# ESP32.net
KiCad netlist of a schematic drawn in EAGLE
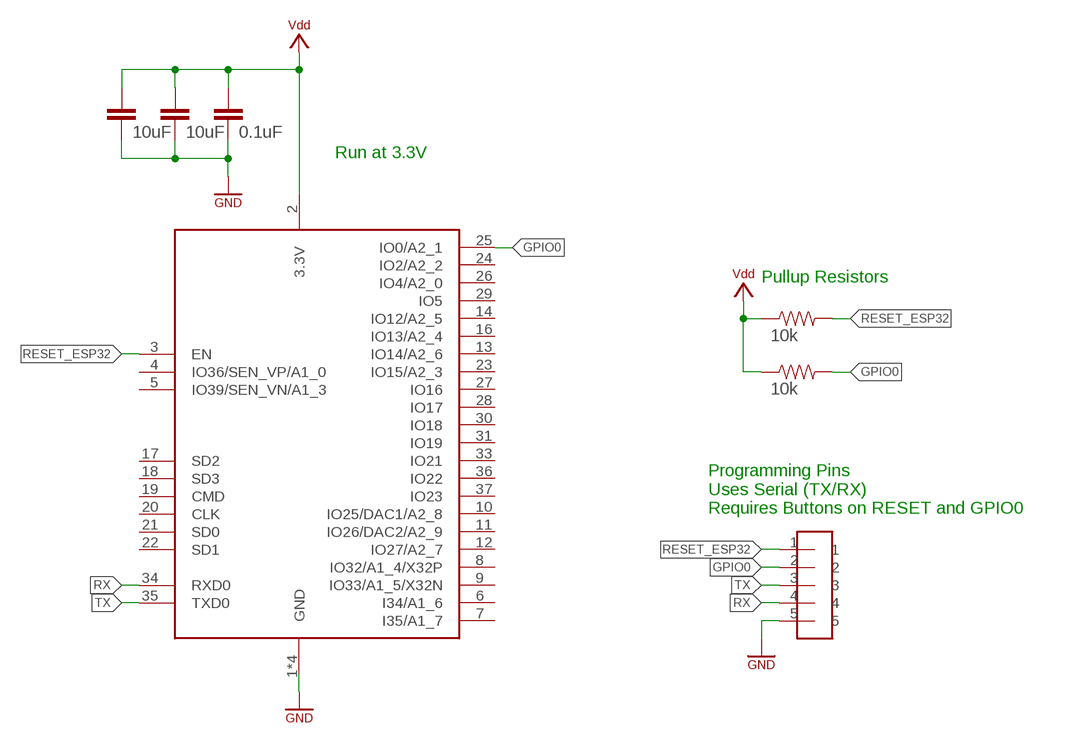
[diagram p0: schematic, sheet 1]

(export (version "E")
  (design (tool "Eeschema 10.0.6"))
  (components
    (comp (ref "C1")
      (value "0.1uF")
      (footprint "eagle-import:0805")
      (libsource (lib "eagle-import") (part "COMPONENT_CAP-0805"))
    )
    (comp (ref "C2")
      (value "10uF")
      (footprint "eagle-import:0805")
      (libsource (lib "eagle-import") (part "COMPONENT_CAP-0805"))
    )
    (comp (ref "C3")
      (value "10uF")
      (footprint "eagle-import:0805")
      (libsource (lib "eagle-import") (part "COMPONENT_CAP-0805"))
    )
    (comp (ref "R1")
      (value "10k")
      (footprint "eagle-import:0805")
      (libsource (lib "eagle-import") (part "COMPONENT_RESISTOR-0805"))
    )
    (comp (ref "R2")
      (value "10k")
      (footprint "eagle-import:0805")
      (libsource (lib "eagle-import") (part "COMPONENT_RESISTOR-0805"))
    )
    (comp (ref "U$1")
      (value "HEADER-5-TESTPOINT")
      (footprint "eagle-import:TESTPOINT-5")
      (libsource (lib "eagle-import") (part "HEADER-5-TESTPOINT"))
    )
    (comp (ref "X1")
      (value "MICRO_ESP32")
      (footprint "eagle-import:WROOM32")
      (libsource (lib "eagle-import") (part "MICRO_ESP32"))
    )
  )
  (nets
    (net (code "1") (name "GPIO0") (class "Default")
      (node (ref "R2") (pin "2") (pinfunction "2_2") (pintype "passive"))
      (node (ref "U$1") (pin "2") (pinfunction "2_2") (pintype "bidirectional"))
      (node (ref "X1") (pin "25") (pinfunction "IO0/A2_1_25") (pintype "bidirectional"))
    )
    (net (code "2") (name "RESET_ESP32") (class "Default")
      (node (ref "R1") (pin "2") (pinfunction "2_2") (pintype "passive"))
      (node (ref "U$1") (pin "1") (pinfunction "1_1") (pintype "bidirectional"))
      (node (ref "X1") (pin "3") (pinfunction "EN_3") (pintype "input"))
    )
    (net (code "3") (name "RX") (class "Default")
      (node (ref "U$1") (pin "4") (pinfunction "4_4") (pintype "bidirectional"))
      (node (ref "X1") (pin "34") (pinfunction "RXD0_34") (pintype "input"))
    )
    (net (code "4") (name "SYMBOL_GND") (class "Default")
      (node (ref "C1") (pin "2") (pinfunction "2_2") (pintype "passive"))
      (node (ref "C2") (pin "2") (pinfunction "2_2") (pintype "passive"))
      (node (ref "C3") (pin "2") (pinfunction "2_2") (pintype "passive"))
      (node (ref "U$1") (pin "5") (pinfunction "5_5") (pintype "bidirectional"))
      (node (ref "X1") (pin "1") (pinfunction "GND_1") (pintype "passive"))
      (node (ref "X1") (pin "15") (pinfunction "GND_15") (pintype "passive"))
      (node (ref "X1") (pin "38") (pinfunction "GND_38") (pintype "passive"))
      (node (ref "X1") (pin "P$1") (pinfunction "GND_P$1") (pintype "passive"))
    )
    (net (code "5") (name "SYMBOL_VDD") (class "Default")
      (node (ref "C1") (pin "1") (pinfunction "1_1") (pintype "passive"))
      (node (ref "C2") (pin "1") (pinfunction "1_1") (pintype "passive"))
      (node (ref "C3") (pin "1") (pinfunction "1_1") (pintype "passive"))
      (node (ref "R1") (pin "1") (pinfunction "1_1") (pintype "passive"))
      (node (ref "R2") (pin "1") (pinfunction "1_1") (pintype "passive"))
      (node (ref "X1") (pin "2") (pinfunction "3.3V_2") (pintype "passive"))
    )
    (net (code "6") (name "TX") (class "Default")
      (node (ref "U$1") (pin "3") (pinfunction "3_3") (pintype "bidirectional"))
      (node (ref "X1") (pin "35") (pinfunction "TXD0_35") (pintype "output"))
    )
    (net (code "7") (name "unconnected-(X1-CLK-Pad20)") (class "Default")
      (node (ref "X1") (pin "20") (pinfunction "CLK_20") (pintype "bidirectional"))
    )
    (net (code "8") (name "unconnected-(X1-CMD-Pad19)") (class "Default")
      (node (ref "X1") (pin "19") (pinfunction "CMD_19") (pintype "bidirectional"))
    )
    (net (code "9") (name "unconnected-(X1-I34{slash}A1_6-Pad6)") (class "Default")
      (node (ref "X1") (pin "6") (pinfunction "I34/A1_6_6") (pintype "bidirectional"))
    )
    (net (code "10") (name "unconnected-(X1-I35{slash}A1_7-Pad7)") (class "Default")
      (node (ref "X1") (pin "7") (pinfunction "I35/A1_7_7") (pintype "bidirectional"))
    )
    (net (code "11") (name "unconnected-(X1-IO2{slash}A2_2-Pad24)") (class "Default")
      (node (ref "X1") (pin "24") (pinfunction "IO2/A2_2_24") (pintype "bidirectional"))
    )
    (net (code "12") (name "unconnected-(X1-IO4{slash}A2_0-Pad26)") (class "Default")
      (node (ref "X1") (pin "26") (pinfunction "IO4/A2_0_26") (pintype "bidirectional"))
    )
    (net (code "13") (name "unconnected-(X1-IO5-Pad29)") (class "Default")
      (node (ref "X1") (pin "29") (pinfunction "IO5_29") (pintype "bidirectional"))
    )
    (net (code "14") (name "unconnected-(X1-IO12{slash}A2_5-Pad14)") (class "Default")
      (node (ref "X1") (pin "14") (pinfunction "IO12/A2_5_14") (pintype "bidirectional"))
    )
    (net (code "15") (name "unconnected-(X1-IO13{slash}A2_4-Pad16)") (class "Default")
      (node (ref "X1") (pin "16") (pinfunction "IO13/A2_4_16") (pintype "bidirectional"))
    )
    (net (code "16") (name "unconnected-(X1-IO14{slash}A2_6-Pad13)") (class "Default")
      (node (ref "X1") (pin "13") (pinfunction "IO14/A2_6_13") (pintype "bidirectional"))
    )
    (net (code "17") (name "unconnected-(X1-IO15{slash}A2_3-Pad23)") (class "Default")
      (node (ref "X1") (pin "23") (pinfunction "IO15/A2_3_23") (pintype "bidirectional"))
    )
    (net (code "18") (name "unconnected-(X1-IO16-Pad27)") (class "Default")
      (node (ref "X1") (pin "27") (pinfunction "IO16_27") (pintype "bidirectional"))
    )
    (net (code "19") (name "unconnected-(X1-IO17-Pad28)") (class "Default")
      (node (ref "X1") (pin "28") (pinfunction "IO17_28") (pintype "bidirectional"))
    )
    (net (code "20") (name "unconnected-(X1-IO18-Pad30)") (class "Default")
      (node (ref "X1") (pin "30") (pinfunction "IO18_30") (pintype "bidirectional"))
    )
    (net (code "21") (name "unconnected-(X1-IO19-Pad31)") (class "Default")
      (node (ref "X1") (pin "31") (pinfunction "IO19_31") (pintype "bidirectional"))
    )
    (net (code "22") (name "unconnected-(X1-IO21-Pad33)") (class "Default")
      (node (ref "X1") (pin "33") (pinfunction "IO21_33") (pintype "bidirectional"))
    )
    (net (code "23") (name "unconnected-(X1-IO22-Pad36)") (class "Default")
      (node (ref "X1") (pin "36") (pinfunction "IO22_36") (pintype "bidirectional"))
    )
    (net (code "24") (name "unconnected-(X1-IO23-Pad37)") (class "Default")
      (node (ref "X1") (pin "37") (pinfunction "IO23_37") (pintype "bidirectional"))
    )
    (net (code "25") (name "unconnected-(X1-IO25{slash}DAC1{slash}A2_8-Pad10)") (class "Default")
      (node (ref "X1") (pin "10") (pinfunction "IO25/DAC1/A2_8_10") (pintype "bidirectional"))
    )
    (net (code "26") (name "unconnected-(X1-IO26{slash}DAC2{slash}A2_9-Pad11)") (class "Default")
      (node (ref "X1") (pin "11") (pinfunction "IO26/DAC2/A2_9_11") (pintype "bidirectional"))
    )
    (net (code "27") (name "unconnected-(X1-IO27{slash}A2_7-Pad12)") (class "Default")
      (node (ref "X1") (pin "12") (pinfunction "IO27/A2_7_12") (pintype "bidirectional"))
    )
    (net (code "28") (name "unconnected-(X1-IO32{slash}A1_4{slash}X32P-Pad8)") (class "Default")
      (node (ref "X1") (pin "8") (pinfunction "IO32/A1_4/X32P_8") (pintype "bidirectional"))
    )
    (net (code "29") (name "unconnected-(X1-IO33{slash}A1_5{slash}X32N-Pad9)") (class "Default")
      (node (ref "X1") (pin "9") (pinfunction "IO33/A1_5/X32N_9") (pintype "bidirectional"))
    )
    (net (code "30") (name "unconnected-(X1-IO36{slash}SEN_VP{slash}A1_0-Pad4)") (class "Default")
      (node (ref "X1") (pin "4") (pinfunction "IO36/SEN_VP/A1_0_4") (pintype "passive"))
    )
    (net (code "31") (name "unconnected-(X1-IO39{slash}SEN_VN{slash}A1_3-Pad5)") (class "Default")
      (node (ref "X1") (pin "5") (pinfunction "IO39/SEN_VN/A1_3_5") (pintype "passive"))
    )
    (net (code "32") (name "unconnected-(X1-SD0-Pad21)") (class "Default")
      (node (ref "X1") (pin "21") (pinfunction "SD0_21") (pintype "bidirectional"))
    )
    (net (code "33") (name "unconnected-(X1-SD1-Pad22)") (class "Default")
      (node (ref "X1") (pin "22") (pinfunction "SD1_22") (pintype "bidirectional"))
    )
    (net (code "34") (name "unconnected-(X1-SD2-Pad17)") (class "Default")
      (node (ref "X1") (pin "17") (pinfunction "SD2_17") (pintype "bidirectional"))
    )
    (net (code "35") (name "unconnected-(X1-SD3-Pad18)") (class "Default")
      (node (ref "X1") (pin "18") (pinfunction "SD3_18") (pintype "bidirectional"))
    )
  )
)
